# LoPoSwitchWiFi_v2.net
KiCad netlist of a schematic drawn in EasyEDA
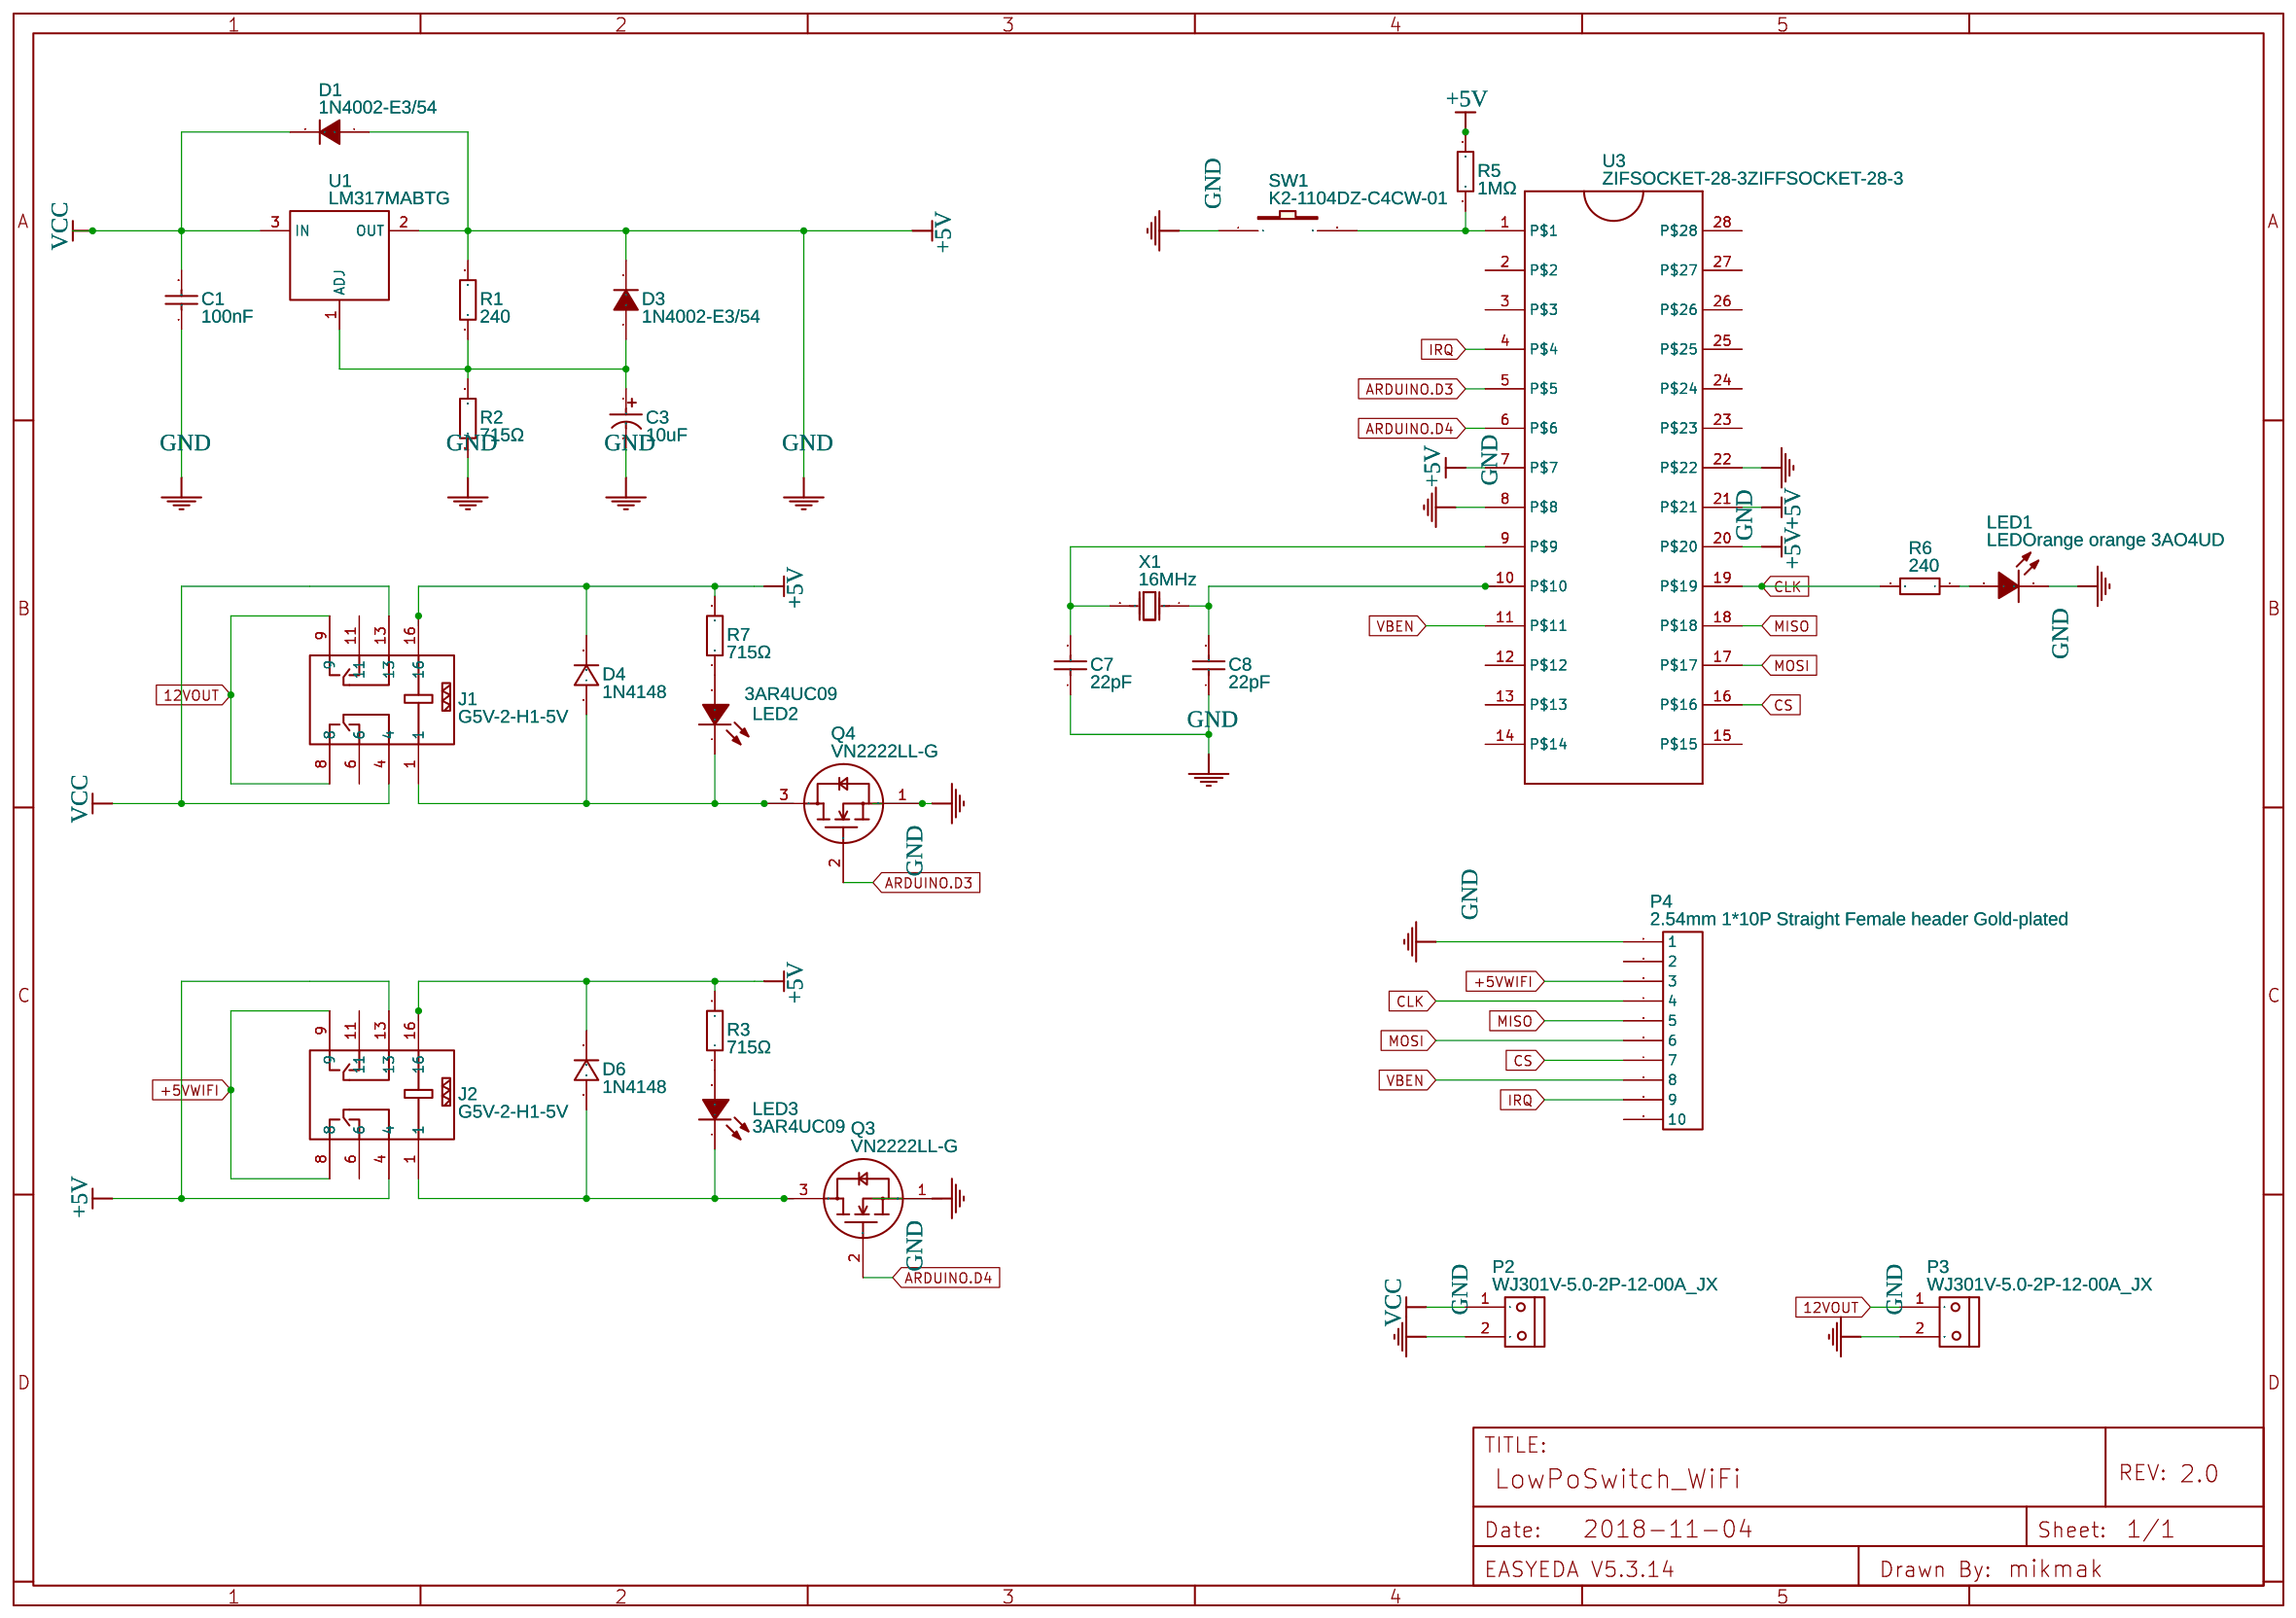
[diagram p0: schematic sheet]

(export (version "E")
  (design (tool "Eeschema 10.0.6"))
  (components
    (comp (ref "C1")
      (value "100nF")
      (fields
        (field (name "BOM_Manufacturer Part") "MPP104K5130508LC")
        (field (name "BOM_Supplier Part") "C109523")
      )
      (libsource (lib "") (part "MPP104K5130508LC"))
    )
    (comp (ref "C3")
      (value "10uF")
      (fields (field (name "BOM_Manufacturer Part") "10uf/100V") (field (name "BOM_Supplier Part") "C2029"))
      (libsource (lib "") (part "10uf/100V"))
    )
    (comp (ref "C7")
      (value "22pF")
      (fields
        (field (name "BOM_Manufacturer Part") "Monolithic0603N220J500")
        (field (name "BOM_Supplier Part") "C110283")
      )
      (libsource (lib "") (part "Monolithic0603N220J500"))
    )
    (comp (ref "C8")
      (value "22pF")
      (fields
        (field (name "BOM_Manufacturer Part") "Monolithic0603N220J500")
        (field (name "BOM_Supplier Part") "C110283")
      )
      (libsource (lib "") (part "Monolithic0603N220J500"))
    )
    (comp (ref "D1")
      (value "1N4002-E3/54")
      (fields (field (name "BOM_Supplier Part") "C33504"))
      (libsource (lib "") (part "Unknown_160_60"))
    )
    (comp (ref "D3")
      (value "1N4002-E3/54")
      (fields (field (name "BOM_Supplier Part") "C33504"))
      (libsource (lib "") (part "Unknown_310_145"))
    )
    (comp (ref "D4")
      (value "1N4148")
      (fields (field (name "BOM_Supplier Part") "C163750"))
      (libsource (lib "") (part "Unknown_290_335"))
    )
    (comp (ref "D6")
      (value "1N4148")
      (fields (field (name "BOM_Supplier Part") "C163750"))
      (libsource (lib "") (part "Unknown_290_535"))
    )
    (comp (ref "J1")
      (value "G5V-2-H1-5V")
      (fields (field (name "BOM_Supplier Part") "C28066"))
      (libsource (lib "") (part "Unknown_185_340"))
    )
    (comp (ref "J2")
      (value "G5V-2-H1-5V")
      (fields (field (name "BOM_Supplier Part") "C28066"))
      (libsource (lib "") (part "Unknown_185_540"))
    )
    (comp (ref "LED1")
      (value "LEDOrange orange 3AO4UD")
      (fields (field (name "BOM_Supplier Part") "C62095"))
      (libsource (lib "") (part "Unknown_1010_290"))
    )
    (comp (ref "LED2")
      (value "3AR4UC09")
      (fields (field (name "BOM_Supplier Part") "C6211"))
      (libsource (lib "") (part "Unknown_355_355"))
    )
    (comp (ref "LED3")
      (value "3AR4UC09")
      (fields (field (name "BOM_Supplier Part") "C6211"))
      (libsource (lib "") (part "Unknown_355_555"))
    )
    (comp (ref "P2")
      (value "WJ301V-5.0-2P-12-00A_JX")
      (fields (field (name "BOM_Manufacturer Part") "?") (field (name "BOM_Supplier Part") "C72326"))
      (libsource (lib "") (part "Unknown_755_655"))
    )
    (comp (ref "P3")
      (value "WJ301V-5.0-2P-12-00A_JX")
      (fields (field (name "BOM_Manufacturer Part") "?") (field (name "BOM_Supplier Part") "C72326"))
      (libsource (lib "") (part "Unknown_975_655"))
    )
    (comp (ref "P4")
      (value "2.54mm 1*10P Straight Female header Gold-plated")
      (fields (field (name "BOM_Supplier Part") "C35445"))
      (libsource (lib "") (part "Unknown_825_510"))
    )
    (comp (ref "Q3")
      (value "VN2222LL-G")
      (fields (field (name "BOM_Supplier Part") "C152170"))
      (libsource (lib "") (part "Unknown_430_610"))
    )
    (comp (ref "Q4")
      (value "VN2222LL-G")
      (fields (field (name "BOM_Supplier Part") "C152170"))
      (libsource (lib "") (part "Unknown_420_410"))
    )
    (comp (ref "R1")
      (value "240")
      (fields
        (field (name "BOM_Manufacturer Part") "MF1/8W-240Ω±1% T52")
        (field (name "BOM_Supplier Part") "C119165")
      )
      (libsource (lib "") (part "MF1/8W-240Ω±1% T52"))
    )
    (comp (ref "R2")
      (value "715Ω")
      (fields
        (field (name "BOM_Manufacturer Part") "0603WAF7150T5E")
        (field (name "BOM_Supplier Part") "C23238")
      )
      (libsource (lib "") (part "0603WAF7150T5E"))
    )
    (comp (ref "R3")
      (value "715Ω")
      (fields
        (field (name "BOM_Manufacturer Part") "0603WAF7150T5E")
        (field (name "BOM_Supplier Part") "C23238")
      )
      (libsource (lib "") (part "0603WAF7150T5E"))
    )
    (comp (ref "R5")
      (value "1MΩ")
      (fields
        (field (name "BOM_Manufacturer Part") "MFR0W4F1004A50")
        (field (name "BOM_Supplier Part") "C58596")
      )
      (libsource (lib "") (part "MFR0W4F1004A50"))
    )
    (comp (ref "R6")
      (value "240")
      (fields
        (field (name "BOM_Manufacturer Part") "MF1/8W-240Ω±1% T52")
        (field (name "BOM_Supplier Part") "C119165")
      )
      (libsource (lib "") (part "MF1/8W-240Ω±1% T52_1"))
    )
    (comp (ref "R7")
      (value "715Ω")
      (fields
        (field (name "BOM_Manufacturer Part") "0603WAF7150T5E")
        (field (name "BOM_Supplier Part") "C23238")
      )
      (libsource (lib "") (part "0603WAF7150T5E"))
    )
    (comp (ref "SW1")
      (value "K2-1104DZ-C4CW-01")
      (fields (field (name "BOM_Supplier Part") "C145889"))
      (libsource (lib "") (part "Unknown_640_110"))
    )
    (comp (ref "U1")
      (value "LM317MABTG")
      (fields (field (name "BOM_Supplier Part") "C94823"))
      (libsource (lib "") (part "Unknown_165_120"))
    )
    (comp (ref "U3")
      (value "ZIFSOCKET-28-3ZIFFSOCKET-28-3")
      (fields (field (name "BOM_Manufacturer Part") "?"))
      (libsource (lib "") (part "Unknown_765_390"))
    )
    (comp (ref "X1")
      (value "16MHz")
      (fields
        (field (name "BOM_Manufacturer Part") "X49SD16MSD2SC")
        (field (name "BOM_Supplier Part") "C16212")
      )
      (libsource (lib "") (part "X49SD16MSD2SC"))
    )
  )
  (nets
    (net (code "1") (name "+5V") (class "Default")
      (node (ref "C1") (pin "1") (pinfunction "1_1") (pintype "input"))
      (node (ref "C3") (pin "2") (pinfunction "2_2") (pintype "input"))
      (node (ref "C7") (pin "1") (pinfunction "1_1") (pintype "input"))
      (node (ref "C8") (pin "1") (pinfunction "1_1") (pintype "input"))
      (node (ref "D1") (pin "1") (pinfunction "A_1") (pintype "unspecified"))
      (node (ref "D3") (pin "2") (pinfunction "K_2") (pintype "unspecified"))
      (node (ref "D4") (pin "2") (pinfunction "2_2") (pintype "unspecified"))
      (node (ref "D6") (pin "2") (pinfunction "2_2") (pintype "unspecified"))
      (node (ref "J1") (pin "16") (pinfunction "16_16") (pintype "unspecified"))
      (node (ref "J2") (pin "13") (pinfunction "13_13") (pintype "unspecified"))
      (node (ref "J2") (pin "16") (pinfunction "16_16") (pintype "unspecified"))
      (node (ref "J2") (pin "4") (pinfunction "4_4") (pintype "unspecified"))
      (node (ref "LED1") (pin "1") (pinfunction "K_1") (pintype "unspecified"))
      (node (ref "P2") (pin "2") (pinfunction "2_2") (pintype "unspecified"))
      (node (ref "P3") (pin "2") (pinfunction "2_2") (pintype "unspecified"))
      (node (ref "P4") (pin "1") (pinfunction "1_1") (pintype "input"))
      (node (ref "Q4") (pin "1") (pinfunction "S_1") (pintype "unspecified"))
      (node (ref "R1") (pin "2") (pinfunction "2_2") (pintype "input"))
      (node (ref "R2") (pin "1") (pinfunction "1_1") (pintype "input"))
      (node (ref "R3") (pin "2") (pinfunction "2_2") (pintype "input"))
      (node (ref "R5") (pin "2") (pinfunction "2_2") (pintype "input"))
      (node (ref "R7") (pin "2") (pinfunction "2_2") (pintype "input"))
      (node (ref "SW1") (pin "1") (pinfunction "1_1") (pintype "input"))
      (node (ref "U1") (pin "2") (pinfunction "OUT_2") (pintype "unspecified"))
      (node (ref "U3") (pin "20") (pinfunction "P$20_20") (pintype "unspecified"))
      (node (ref "U3") (pin "21") (pinfunction "P$21_21") (pintype "unspecified"))
      (node (ref "U3") (pin "22") (pinfunction "P$22_22") (pintype "unspecified"))
      (node (ref "U3") (pin "7") (pinfunction "P$7_7") (pintype "unspecified"))
      (node (ref "U3") (pin "8") (pinfunction "P$8_8") (pintype "unspecified"))
    )
    (net (code "2") (name "+5VWIFI") (class "Default")
      (node (ref "J2") (pin "8") (pinfunction "8_8") (pintype "unspecified"))
      (node (ref "J2") (pin "9") (pinfunction "9_9") (pintype "unspecified"))
      (node (ref "P4") (pin "3") (pinfunction "3_3") (pintype "input"))
    )
    (net (code "3") (name "12VOUT") (class "Default")
      (node (ref "J1") (pin "8") (pinfunction "8_8") (pintype "unspecified"))
      (node (ref "J1") (pin "9") (pinfunction "9_9") (pintype "unspecified"))
      (node (ref "P3") (pin "1") (pinfunction "1_1") (pintype "unspecified"))
    )
    (net (code "4") (name "ARDUINO.D3") (class "Default")
      (node (ref "Q4") (pin "2") (pinfunction "G_2") (pintype "unspecified"))
      (node (ref "U3") (pin "5") (pinfunction "P$5_5") (pintype "unspecified"))
    )
    (net (code "5") (name "ARDUINO.D4") (class "Default")
      (node (ref "Q3") (pin "2") (pinfunction "G_2") (pintype "unspecified"))
      (node (ref "U3") (pin "6") (pinfunction "P$6_6") (pintype "unspecified"))
    )
    (net (code "6") (name "CLK") (class "Default")
      (node (ref "P4") (pin "4") (pinfunction "4_4") (pintype "input"))
      (node (ref "R6") (pin "2") (pinfunction "2_2") (pintype "input"))
      (node (ref "U3") (pin "19") (pinfunction "P$19_19") (pintype "unspecified"))
    )
    (net (code "7") (name "CS") (class "Default")
      (node (ref "P4") (pin "7") (pinfunction "7_7") (pintype "input"))
      (node (ref "U3") (pin "16") (pinfunction "P$16_16") (pintype "unspecified"))
    )
    (net (code "8") (name "IRQ") (class "Default")
      (node (ref "P4") (pin "9") (pinfunction "9_9") (pintype "input"))
      (node (ref "U3") (pin "4") (pinfunction "P$4_4") (pintype "unspecified"))
    )
    (net (code "9") (name "MISO") (class "Default")
      (node (ref "P4") (pin "5") (pinfunction "5_5") (pintype "input"))
      (node (ref "U3") (pin "18") (pinfunction "P$18_18") (pintype "unspecified"))
    )
    (net (code "10") (name "MOSI") (class "Default")
      (node (ref "P4") (pin "6") (pinfunction "6_6") (pintype "input"))
      (node (ref "U3") (pin "17") (pinfunction "P$17_17") (pintype "unspecified"))
    )
    (net (code "11") (name "Net-(D3-A)") (class "Default")
      (node (ref "C3") (pin "1") (pinfunction "1_1") (pintype "input"))
      (node (ref "D3") (pin "1") (pinfunction "A_1") (pintype "unspecified"))
      (node (ref "R1") (pin "1") (pinfunction "1_1") (pintype "input"))
      (node (ref "R2") (pin "2") (pinfunction "2_2") (pintype "input"))
      (node (ref "U1") (pin "1") (pinfunction "ADJ_1") (pintype "input"))
    )
    (net (code "12") (name "Net-(LED1-A)") (class "Default")
      (node (ref "LED1") (pin "2") (pinfunction "A_2") (pintype "unspecified"))
      (node (ref "R6") (pin "1") (pinfunction "1_1") (pintype "input"))
    )
    (net (code "13") (name "Net-(LED2-A)") (class "Default")
      (node (ref "LED2") (pin "2") (pinfunction "A_2") (pintype "unspecified"))
      (node (ref "R7") (pin "1") (pinfunction "1_1") (pintype "input"))
    )
    (net (code "14") (name "Net-(LED2-K)") (class "Default")
      (node (ref "D4") (pin "1") (pinfunction "1_1") (pintype "unspecified"))
      (node (ref "J1") (pin "1") (pinfunction "1_1") (pintype "unspecified"))
      (node (ref "LED2") (pin "1") (pinfunction "K_1") (pintype "unspecified"))
      (node (ref "Q4") (pin "3") (pinfunction "D_3") (pintype "unspecified"))
    )
    (net (code "15") (name "Net-(LED3-A)") (class "Default")
      (node (ref "LED3") (pin "2") (pinfunction "A_2") (pintype "unspecified"))
      (node (ref "R3") (pin "1") (pinfunction "1_1") (pintype "input"))
    )
    (net (code "16") (name "Net-(LED3-K)") (class "Default")
      (node (ref "D6") (pin "1") (pinfunction "1_1") (pintype "unspecified"))
      (node (ref "J2") (pin "1") (pinfunction "1_1") (pintype "unspecified"))
      (node (ref "LED3") (pin "1") (pinfunction "K_1") (pintype "unspecified"))
      (node (ref "Q3") (pin "3") (pinfunction "D_3") (pintype "unspecified"))
    )
    (net (code "17") (name "Net-(U3-P$1)") (class "Default")
      (node (ref "R5") (pin "1") (pinfunction "1_1") (pintype "input"))
      (node (ref "SW1") (pin "2") (pinfunction "2_2") (pintype "input"))
      (node (ref "U3") (pin "1") (pinfunction "P$1_1") (pintype "unspecified"))
    )
    (net (code "18") (name "Net-(U3-P$9)") (class "Default")
      (node (ref "C7") (pin "2") (pinfunction "2_2") (pintype "input"))
      (node (ref "U3") (pin "9") (pinfunction "P$9_9") (pintype "unspecified"))
      (node (ref "X1") (pin "2") (pinfunction "OSC2_2") (pintype "input"))
    )
    (net (code "19") (name "Net-(U3-P$10)") (class "Default")
      (node (ref "C8") (pin "2") (pinfunction "2_2") (pintype "input"))
      (node (ref "U3") (pin "10") (pinfunction "P$10_10") (pintype "unspecified"))
      (node (ref "X1") (pin "1") (pinfunction "OSC1_1") (pintype "input"))
    )
    (net (code "20") (name "VBEN") (class "Default")
      (node (ref "P4") (pin "8") (pinfunction "8_8") (pintype "input"))
      (node (ref "U3") (pin "11") (pinfunction "P$11_11") (pintype "unspecified"))
    )
    (net (code "21") (name "VCC") (class "Default")
      (node (ref "C1") (pin "2") (pinfunction "2_2") (pintype "input"))
      (node (ref "D1") (pin "2") (pinfunction "K_2") (pintype "unspecified"))
      (node (ref "J1") (pin "13") (pinfunction "13_13") (pintype "unspecified"))
      (node (ref "J1") (pin "4") (pinfunction "4_4") (pintype "unspecified"))
      (node (ref "P2") (pin "1") (pinfunction "1_1") (pintype "unspecified"))
      (node (ref "U1") (pin "3") (pinfunction "IN_3") (pintype "input"))
    )
    (net (code "22") (name "unconnected-(J1-Pad6)") (class "Default")
      (node (ref "J1") (pin "6") (pinfunction "6_6") (pintype "unspecified"))
    )
    (net (code "23") (name "unconnected-(J1-Pad11)") (class "Default")
      (node (ref "J1") (pin "11") (pinfunction "11_11") (pintype "unspecified"))
    )
    (net (code "24") (name "unconnected-(J2-Pad6)") (class "Default")
      (node (ref "J2") (pin "6") (pinfunction "6_6") (pintype "unspecified"))
    )
    (net (code "25") (name "unconnected-(J2-Pad11)") (class "Default")
      (node (ref "J2") (pin "11") (pinfunction "11_11") (pintype "unspecified"))
    )
    (net (code "26") (name "unconnected-(P4-Pad2)") (class "Default")
      (node (ref "P4") (pin "2") (pinfunction "2_2") (pintype "input"))
    )
    (net (code "27") (name "unconnected-(P4-Pad10)") (class "Default")
      (node (ref "P4") (pin "10") (pinfunction "10_10") (pintype "input"))
    )
    (net (code "28") (name "unconnected-(Q3-S-Pad1)") (class "Default")
      (node (ref "Q3") (pin "1") (pinfunction "S_1") (pintype "unspecified"))
    )
    (net (code "29") (name "unconnected-(U3-P$2-Pad2)") (class "Default")
      (node (ref "U3") (pin "2") (pinfunction "P$2_2") (pintype "unspecified"))
    )
    (net (code "30") (name "unconnected-(U3-P$3-Pad3)") (class "Default")
      (node (ref "U3") (pin "3") (pinfunction "P$3_3") (pintype "unspecified"))
    )
    (net (code "31") (name "unconnected-(U3-P$12-Pad12)") (class "Default")
      (node (ref "U3") (pin "12") (pinfunction "P$12_12") (pintype "unspecified"))
    )
    (net (code "32") (name "unconnected-(U3-P$13-Pad13)") (class "Default")
      (node (ref "U3") (pin "13") (pinfunction "P$13_13") (pintype "unspecified"))
    )
    (net (code "33") (name "unconnected-(U3-P$14-Pad14)") (class "Default")
      (node (ref "U3") (pin "14") (pinfunction "P$14_14") (pintype "unspecified"))
    )
    (net (code "34") (name "unconnected-(U3-P$15-Pad15)") (class "Default")
      (node (ref "U3") (pin "15") (pinfunction "P$15_15") (pintype "unspecified"))
    )
    (net (code "35") (name "unconnected-(U3-P$23-Pad23)") (class "Default")
      (node (ref "U3") (pin "23") (pinfunction "P$23_23") (pintype "unspecified"))
    )
    (net (code "36") (name "unconnected-(U3-P$24-Pad24)") (class "Default")
      (node (ref "U3") (pin "24") (pinfunction "P$24_24") (pintype "unspecified"))
    )
    (net (code "37") (name "unconnected-(U3-P$25-Pad25)") (class "Default")
      (node (ref "U3") (pin "25") (pinfunction "P$25_25") (pintype "unspecified"))
    )
    (net (code "38") (name "unconnected-(U3-P$26-Pad26)") (class "Default")
      (node (ref "U3") (pin "26") (pinfunction "P$26_26") (pintype "unspecified"))
    )
    (net (code "39") (name "unconnected-(U3-P$27-Pad27)") (class "Default")
      (node (ref "U3") (pin "27") (pinfunction "P$27_27") (pintype "unspecified"))
    )
    (net (code "40") (name "unconnected-(U3-P$28-Pad28)") (class "Default")
      (node (ref "U3") (pin "28") (pinfunction "P$28_28") (pintype "unspecified"))
    )
  )
)
